# work.net
KiCad netlist of a schematic drawn in Altium Designer
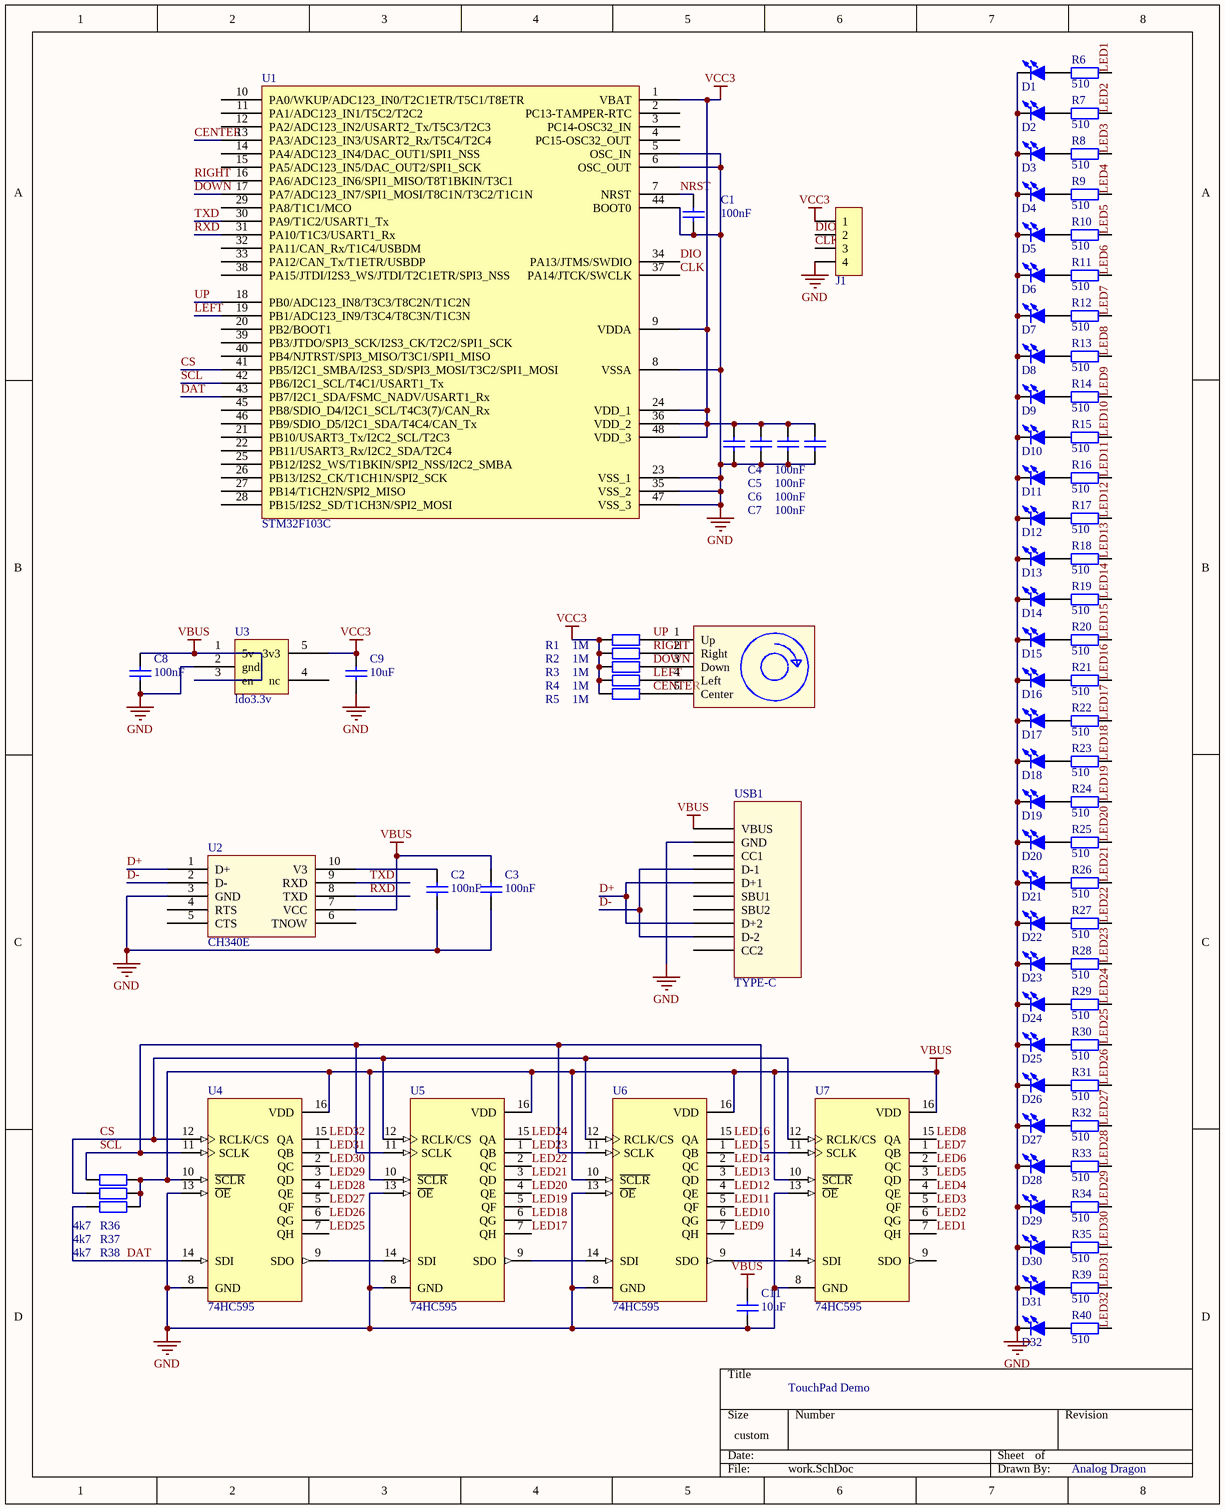
[diagram p0: work.SchDoc]

(export (version "E")
  (design (tool "Eeschema 10.0.6"))
  (components
    (comp (ref "*1")
      (value "TouchPad-R")
      (footprint "TouchPad-R")
      (libsource (lib "fszhang") (part "TouchPad-R"))
    )
    (comp (ref "C1")
      (value "100nF")
      (footprint "C-RAD-0603")
      (description "无极性电容")
      (fields (field (name "Comment") "Cap") (field (name "PUBLISHER") "Altium Limited"))
      (libsource (lib "fszhang") (part "Cap"))
    )
    (comp (ref "C2")
      (value "100nF")
      (footprint "C-RAD-0603")
      (description "无极性电容")
      (fields (field (name "Comment") "Cap") (field (name "PUBLISHER") "Altium Limited"))
      (libsource (lib "fszhang") (part "Cap"))
    )
    (comp (ref "C3")
      (value "100nF")
      (footprint "C-RAD-0603")
      (description "无极性电容")
      (fields (field (name "Comment") "Cap") (field (name "PUBLISHER") "Altium Limited"))
      (libsource (lib "fszhang") (part "Cap"))
    )
    (comp (ref "C4")
      (value "100nF")
      (footprint "C-RAD-0603")
      (description "无极性电容")
      (fields (field (name "Comment") "Cap") (field (name "PUBLISHER") "Altium Limited"))
      (libsource (lib "fszhang") (part "Cap"))
    )
    (comp (ref "C5")
      (value "100nF")
      (footprint "C-RAD-0603")
      (description "无极性电容")
      (fields (field (name "Comment") "Cap") (field (name "PUBLISHER") "Altium Limited"))
      (libsource (lib "fszhang") (part "Cap"))
    )
    (comp (ref "C6")
      (value "100nF")
      (footprint "C-RAD-0603")
      (description "无极性电容")
      (fields (field (name "Comment") "Cap") (field (name "PUBLISHER") "Altium Limited"))
      (libsource (lib "fszhang") (part "Cap"))
    )
    (comp (ref "C7")
      (value "100nF")
      (footprint "C-RAD-0603")
      (description "无极性电容")
      (fields (field (name "Comment") "Cap") (field (name "PUBLISHER") "Altium Limited"))
      (libsource (lib "fszhang") (part "Cap"))
    )
    (comp (ref "C8")
      (value "100nF")
      (footprint "C-RAD-3528")
      (description "无极性电容")
      (fields (field (name "Comment") "Cap") (field (name "PUBLISHER") "Altium Limited"))
      (libsource (lib "fszhang") (part "Cap"))
    )
    (comp (ref "C9")
      (value "10uF")
      (footprint "C-RAD-0805")
      (description "无极性电容")
      (fields (field (name "Comment") "Cap") (field (name "PUBLISHER") "Altium Limited"))
      (libsource (lib "fszhang") (part "Cap"))
    )
    (comp (ref "C11")
      (value "10uF")
      (footprint "C-RAD-0805")
      (description "无极性电容")
      (fields (field (name "Comment") "Cap") (field (name "PUBLISHER") "Altium Limited"))
      (libsource (lib "fszhang") (part "Cap"))
    )
    (comp (ref "D1")
      (value "~")
      (footprint "LED 0805W")
      (description "贴片LED")
      (libsource (lib "9.1   - LED") (part "LED-SMD"))
    )
    (comp (ref "D2")
      (value "~")
      (footprint "LED 0805W")
      (description "贴片LED")
      (libsource (lib "9.1   - LED") (part "LED-SMD"))
    )
    (comp (ref "D3")
      (value "~")
      (footprint "LED 0805W")
      (description "贴片LED")
      (libsource (lib "9.1   - LED") (part "LED-SMD"))
    )
    (comp (ref "D4")
      (value "~")
      (footprint "LED 0805W")
      (description "贴片LED")
      (libsource (lib "9.1   - LED") (part "LED-SMD"))
    )
    (comp (ref "D5")
      (value "~")
      (footprint "LED 0805W")
      (description "贴片LED")
      (libsource (lib "9.1   - LED") (part "LED-SMD"))
    )
    (comp (ref "D6")
      (value "~")
      (footprint "LED 0805W")
      (description "贴片LED")
      (libsource (lib "9.1   - LED") (part "LED-SMD"))
    )
    (comp (ref "D7")
      (value "~")
      (footprint "LED 0805W")
      (description "贴片LED")
      (libsource (lib "9.1   - LED") (part "LED-SMD"))
    )
    (comp (ref "D8")
      (value "~")
      (footprint "LED 0805W")
      (description "贴片LED")
      (libsource (lib "9.1   - LED") (part "LED-SMD"))
    )
    (comp (ref "D9")
      (value "~")
      (footprint "LED 0805W")
      (description "贴片LED")
      (libsource (lib "9.1   - LED") (part "LED-SMD"))
    )
    (comp (ref "D10")
      (value "~")
      (footprint "LED 0805W")
      (description "贴片LED")
      (libsource (lib "9.1   - LED") (part "LED-SMD"))
    )
    (comp (ref "D11")
      (value "~")
      (footprint "LED 0805W")
      (description "贴片LED")
      (libsource (lib "9.1   - LED") (part "LED-SMD"))
    )
    (comp (ref "D12")
      (value "~")
      (footprint "LED 0805W")
      (description "贴片LED")
      (libsource (lib "9.1   - LED") (part "LED-SMD"))
    )
    (comp (ref "D13")
      (value "~")
      (footprint "LED 0805W")
      (description "贴片LED")
      (libsource (lib "9.1   - LED") (part "LED-SMD"))
    )
    (comp (ref "D14")
      (value "~")
      (footprint "LED 0805W")
      (description "贴片LED")
      (libsource (lib "9.1   - LED") (part "LED-SMD"))
    )
    (comp (ref "D15")
      (value "~")
      (footprint "LED 0805W")
      (description "贴片LED")
      (libsource (lib "9.1   - LED") (part "LED-SMD"))
    )
    (comp (ref "D16")
      (value "~")
      (footprint "LED 0805W")
      (description "贴片LED")
      (libsource (lib "9.1   - LED") (part "LED-SMD"))
    )
    (comp (ref "D17")
      (value "~")
      (footprint "LED 0805W")
      (description "贴片LED")
      (libsource (lib "9.1   - LED") (part "LED-SMD"))
    )
    (comp (ref "D18")
      (value "~")
      (footprint "LED 0805W")
      (description "贴片LED")
      (libsource (lib "9.1   - LED") (part "LED-SMD"))
    )
    (comp (ref "D19")
      (value "~")
      (footprint "LED 0805W")
      (description "贴片LED")
      (libsource (lib "9.1   - LED") (part "LED-SMD"))
    )
    (comp (ref "D20")
      (value "~")
      (footprint "LED 0805W")
      (description "贴片LED")
      (libsource (lib "9.1   - LED") (part "LED-SMD"))
    )
    (comp (ref "D21")
      (value "~")
      (footprint "LED 0805W")
      (description "贴片LED")
      (libsource (lib "9.1   - LED") (part "LED-SMD"))
    )
    (comp (ref "D22")
      (value "~")
      (footprint "LED 0805W")
      (description "贴片LED")
      (libsource (lib "9.1   - LED") (part "LED-SMD"))
    )
    (comp (ref "D23")
      (value "~")
      (footprint "LED 0805W")
      (description "贴片LED")
      (libsource (lib "9.1   - LED") (part "LED-SMD"))
    )
    (comp (ref "D24")
      (value "~")
      (footprint "LED 0805W")
      (description "贴片LED")
      (libsource (lib "9.1   - LED") (part "LED-SMD"))
    )
    (comp (ref "D25")
      (value "~")
      (footprint "LED 0805W")
      (description "贴片LED")
      (libsource (lib "9.1   - LED") (part "LED-SMD"))
    )
    (comp (ref "D26")
      (value "~")
      (footprint "LED 0805W")
      (description "贴片LED")
      (libsource (lib "9.1   - LED") (part "LED-SMD"))
    )
    (comp (ref "D27")
      (value "~")
      (footprint "LED 0805W")
      (description "贴片LED")
      (libsource (lib "9.1   - LED") (part "LED-SMD"))
    )
    (comp (ref "D28")
      (value "~")
      (footprint "LED 0805W")
      (description "贴片LED")
      (libsource (lib "9.1   - LED") (part "LED-SMD"))
    )
    (comp (ref "D29")
      (value "~")
      (footprint "LED 0805W")
      (description "贴片LED")
      (libsource (lib "9.1   - LED") (part "LED-SMD"))
    )
    (comp (ref "D30")
      (value "~")
      (footprint "LED 0805W")
      (description "贴片LED")
      (libsource (lib "9.1   - LED") (part "LED-SMD"))
    )
    (comp (ref "D31")
      (value "~")
      (footprint "LED 0805W")
      (description "贴片LED")
      (libsource (lib "9.1   - LED") (part "LED-SMD"))
    )
    (comp (ref "D32")
      (value "~")
      (footprint "LED 0805W")
      (description "贴片LED")
      (libsource (lib "9.1   - LED") (part "LED-SMD"))
    )
    (comp (ref "J1")
      (value "HDR-1X4")
      (footprint "HDR2.0-LI-4P")
      (description "4P接插件")
      (libsource (lib "4.5   - 接插件-脚距2.0") (part "Header 4"))
    )
    (comp (ref "R1")
      (value "1M")
      (footprint "0603-1")
      (description "贴片电阻")
      (fields (field (name "Comment") "Res1") (field (name "PUBLISHER") "Altium Limited"))
      (libsource (lib "fszhang") (part "Res1"))
    )
    (comp (ref "R2")
      (value "1M")
      (footprint "0603-1")
      (description "贴片电阻")
      (fields (field (name "Comment") "Res1") (field (name "PUBLISHER") "Altium Limited"))
      (libsource (lib "fszhang") (part "Res1"))
    )
    (comp (ref "R3")
      (value "1M")
      (footprint "0603-1")
      (description "贴片电阻")
      (fields (field (name "Comment") "Res1") (field (name "PUBLISHER") "Altium Limited"))
      (libsource (lib "fszhang") (part "Res1"))
    )
    (comp (ref "R4")
      (value "1M")
      (footprint "0603-1")
      (description "贴片电阻")
      (fields (field (name "Comment") "Res1") (field (name "PUBLISHER") "Altium Limited"))
      (libsource (lib "fszhang") (part "Res1"))
    )
    (comp (ref "R5")
      (value "1M")
      (footprint "0603-1")
      (description "贴片电阻")
      (fields (field (name "Comment") "Res1") (field (name "PUBLISHER") "Altium Limited"))
      (libsource (lib "fszhang") (part "Res1"))
    )
    (comp (ref "R6")
      (value "510")
      (footprint "0603-1")
      (description "贴片电阻")
      (fields (field (name "Comment") "Res1") (field (name "PUBLISHER") "Altium Limited"))
      (libsource (lib "fszhang") (part "Res1"))
    )
    (comp (ref "R7")
      (value "510")
      (footprint "0603-1")
      (description "贴片电阻")
      (fields (field (name "Comment") "Res1") (field (name "PUBLISHER") "Altium Limited"))
      (libsource (lib "fszhang") (part "Res1"))
    )
    (comp (ref "R8")
      (value "510")
      (footprint "0603-1")
      (description "贴片电阻")
      (fields (field (name "Comment") "Res1") (field (name "PUBLISHER") "Altium Limited"))
      (libsource (lib "fszhang") (part "Res1"))
    )
    (comp (ref "R9")
      (value "510")
      (footprint "0603-1")
      (description "贴片电阻")
      (fields (field (name "Comment") "Res1") (field (name "PUBLISHER") "Altium Limited"))
      (libsource (lib "fszhang") (part "Res1"))
    )
    (comp (ref "R10")
      (value "510")
      (footprint "0603-1")
      (description "贴片电阻")
      (fields (field (name "Comment") "Res1") (field (name "PUBLISHER") "Altium Limited"))
      (libsource (lib "fszhang") (part "Res1"))
    )
    (comp (ref "R11")
      (value "510")
      (footprint "0603-1")
      (description "贴片电阻")
      (fields (field (name "Comment") "Res1") (field (name "PUBLISHER") "Altium Limited"))
      (libsource (lib "fszhang") (part "Res1"))
    )
    (comp (ref "R12")
      (value "510")
      (footprint "0603-1")
      (description "贴片电阻")
      (fields (field (name "Comment") "Res1") (field (name "PUBLISHER") "Altium Limited"))
      (libsource (lib "fszhang") (part "Res1"))
    )
    (comp (ref "R13")
      (value "510")
      (footprint "0603-1")
      (description "贴片电阻")
      (fields (field (name "Comment") "Res1") (field (name "PUBLISHER") "Altium Limited"))
      (libsource (lib "fszhang") (part "Res1"))
    )
    (comp (ref "R14")
      (value "510")
      (footprint "0603-1")
      (description "贴片电阻")
      (fields (field (name "Comment") "Res1") (field (name "PUBLISHER") "Altium Limited"))
      (libsource (lib "fszhang") (part "Res1"))
    )
    (comp (ref "R15")
      (value "510")
      (footprint "0603-1")
      (description "贴片电阻")
      (fields (field (name "Comment") "Res1") (field (name "PUBLISHER") "Altium Limited"))
      (libsource (lib "fszhang") (part "Res1"))
    )
    (comp (ref "R16")
      (value "510")
      (footprint "0603-1")
      (description "贴片电阻")
      (fields (field (name "Comment") "Res1") (field (name "PUBLISHER") "Altium Limited"))
      (libsource (lib "fszhang") (part "Res1"))
    )
    (comp (ref "R17")
      (value "510")
      (footprint "0603-1")
      (description "贴片电阻")
      (fields (field (name "Comment") "Res1") (field (name "PUBLISHER") "Altium Limited"))
      (libsource (lib "fszhang") (part "Res1"))
    )
    (comp (ref "R18")
      (value "510")
      (footprint "0603-1")
      (description "贴片电阻")
      (fields (field (name "Comment") "Res1") (field (name "PUBLISHER") "Altium Limited"))
      (libsource (lib "fszhang") (part "Res1"))
    )
    (comp (ref "R19")
      (value "510")
      (footprint "0603-1")
      (description "贴片电阻")
      (fields (field (name "Comment") "Res1") (field (name "PUBLISHER") "Altium Limited"))
      (libsource (lib "fszhang") (part "Res1"))
    )
    (comp (ref "R20")
      (value "510")
      (footprint "0603-1")
      (description "贴片电阻")
      (fields (field (name "Comment") "Res1") (field (name "PUBLISHER") "Altium Limited"))
      (libsource (lib "fszhang") (part "Res1"))
    )
    (comp (ref "R21")
      (value "510")
      (footprint "0603-1")
      (description "贴片电阻")
      (fields (field (name "Comment") "Res1") (field (name "PUBLISHER") "Altium Limited"))
      (libsource (lib "fszhang") (part "Res1"))
    )
    (comp (ref "R22")
      (value "510")
      (footprint "0603-1")
      (description "贴片电阻")
      (fields (field (name "Comment") "Res1") (field (name "PUBLISHER") "Altium Limited"))
      (libsource (lib "fszhang") (part "Res1"))
    )
    (comp (ref "R23")
      (value "510")
      (footprint "0603-1")
      (description "贴片电阻")
      (fields (field (name "Comment") "Res1") (field (name "PUBLISHER") "Altium Limited"))
      (libsource (lib "fszhang") (part "Res1"))
    )
    (comp (ref "R24")
      (value "510")
      (footprint "0603-1")
      (description "贴片电阻")
      (fields (field (name "Comment") "Res1") (field (name "PUBLISHER") "Altium Limited"))
      (libsource (lib "fszhang") (part "Res1"))
    )
    (comp (ref "R25")
      (value "510")
      (footprint "0603-1")
      (description "贴片电阻")
      (fields (field (name "Comment") "Res1") (field (name "PUBLISHER") "Altium Limited"))
      (libsource (lib "fszhang") (part "Res1"))
    )
    (comp (ref "R26")
      (value "510")
      (footprint "0603-1")
      (description "贴片电阻")
      (fields (field (name "Comment") "Res1") (field (name "PUBLISHER") "Altium Limited"))
      (libsource (lib "fszhang") (part "Res1"))
    )
    (comp (ref "R27")
      (value "510")
      (footprint "0603-1")
      (description "贴片电阻")
      (fields (field (name "Comment") "Res1") (field (name "PUBLISHER") "Altium Limited"))
      (libsource (lib "fszhang") (part "Res1"))
    )
    (comp (ref "R28")
      (value "510")
      (footprint "0603-1")
      (description "贴片电阻")
      (fields (field (name "Comment") "Res1") (field (name "PUBLISHER") "Altium Limited"))
      (libsource (lib "fszhang") (part "Res1"))
    )
    (comp (ref "R29")
      (value "510")
      (footprint "0603-1")
      (description "贴片电阻")
      (fields (field (name "Comment") "Res1") (field (name "PUBLISHER") "Altium Limited"))
      (libsource (lib "fszhang") (part "Res1"))
    )
    (comp (ref "R30")
      (value "510")
      (footprint "0603-1")
      (description "贴片电阻")
      (fields (field (name "Comment") "Res1") (field (name "PUBLISHER") "Altium Limited"))
      (libsource (lib "fszhang") (part "Res1"))
    )
    (comp (ref "R31")
      (value "510")
      (footprint "0603-1")
      (description "贴片电阻")
      (fields (field (name "Comment") "Res1") (field (name "PUBLISHER") "Altium Limited"))
      (libsource (lib "fszhang") (part "Res1"))
    )
    (comp (ref "R32")
      (value "510")
      (footprint "0603-1")
      (description "贴片电阻")
      (fields (field (name "Comment") "Res1") (field (name "PUBLISHER") "Altium Limited"))
      (libsource (lib "fszhang") (part "Res1"))
    )
    (comp (ref "R33")
      (value "510")
      (footprint "0603-1")
      (description "贴片电阻")
      (fields (field (name "Comment") "Res1") (field (name "PUBLISHER") "Altium Limited"))
      (libsource (lib "fszhang") (part "Res1"))
    )
    (comp (ref "R34")
      (value "510")
      (footprint "0603-1")
      (description "贴片电阻")
      (fields (field (name "Comment") "Res1") (field (name "PUBLISHER") "Altium Limited"))
      (libsource (lib "fszhang") (part "Res1"))
    )
    (comp (ref "R35")
      (value "510")
      (footprint "0603-1")
      (description "贴片电阻")
      (fields (field (name "Comment") "Res1") (field (name "PUBLISHER") "Altium Limited"))
      (libsource (lib "fszhang") (part "Res1"))
    )
    (comp (ref "R36")
      (value "4k7")
      (footprint "0603-1")
      (description "贴片电阻")
      (fields (field (name "Comment") "Res1") (field (name "PUBLISHER") "Altium Limited"))
      (libsource (lib "fszhang") (part "Res1"))
    )
    (comp (ref "R37")
      (value "4k7")
      (footprint "0603-1")
      (description "贴片电阻")
      (fields (field (name "Comment") "Res1") (field (name "PUBLISHER") "Altium Limited"))
      (libsource (lib "fszhang") (part "Res1"))
    )
    (comp (ref "R38")
      (value "4k7")
      (footprint "0603-1")
      (description "贴片电阻")
      (fields (field (name "Comment") "Res1") (field (name "PUBLISHER") "Altium Limited"))
      (libsource (lib "fszhang") (part "Res1"))
    )
    (comp (ref "R39")
      (value "510")
      (footprint "0603-1")
      (description "贴片电阻")
      (fields (field (name "Comment") "Res1") (field (name "PUBLISHER") "Altium Limited"))
      (libsource (lib "fszhang") (part "Res1"))
    )
    (comp (ref "R40")
      (value "510")
      (footprint "0603-1")
      (description "贴片电阻")
      (fields (field (name "Comment") "Res1") (field (name "PUBLISHER") "Altium Limited"))
      (libsource (lib "fszhang") (part "Res1"))
    )
    (comp (ref "U1")
      (value "STM32F103C")
      (footprint "LQFP-48_M")
      (description "STM32单片机48引脚")
      (libsource (lib "fszhang") (part "STM32F103C"))
    )
    (comp (ref "U2") (value "CH340E") (footprint "MSOP10_M") (libsource (lib "1") (part "CH340E")))
    (comp (ref "U3") (value "ldo3.3v") (footprint "SOT23-5") (libsource (lib "3.3ldo") (part "Component_1")))
    (comp (ref "U4")
      (value "74HC595")
      (footprint "NSO16_M")
      (description "移位寄存器")
      (fields (field (name "PUBLISHER") "Altium Limited"))
      (libsource (lib "fszhang") (part "74HC595"))
    )
    (comp (ref "U5")
      (value "74HC595")
      (footprint "NSO16_M")
      (description "移位寄存器")
      (fields (field (name "PUBLISHER") "Altium Limited"))
      (libsource (lib "fszhang") (part "74HC595"))
    )
    (comp (ref "U6")
      (value "74HC595")
      (footprint "NSO16_M")
      (description "移位寄存器")
      (fields (field (name "PUBLISHER") "Altium Limited"))
      (libsource (lib "fszhang") (part "74HC595"))
    )
    (comp (ref "U7")
      (value "74HC595")
      (footprint "NSO16_M")
      (description "移位寄存器")
      (fields (field (name "PUBLISHER") "Altium Limited"))
      (libsource (lib "fszhang") (part "74HC595"))
    )
    (comp (ref "USB1") (value "TYPE-C") (footprint "TYPE-C") (libsource (lib "1") (part "USB-C")))
  )
  (nets
    (net (code "1") (name "/CENTER") (class "Default")
      (node (ref "*1") (pin "5") (pinfunction "Center_5") (pintype "passive"))
      (node (ref "R5") (pin "2") (pinfunction "2_2") (pintype "passive"))
      (node (ref "U1") (pin "13") (pinfunction "PA3/ADC123_IN3/USART2_Rx/T5C4/T2C4_13") (pintype "passive"))
    )
    (net (code "2") (name "/CLK") (class "Default")
      (node (ref "J1") (pin "3") (pinfunction "3_3") (pintype "passive"))
      (node (ref "U1") (pin "37") (pinfunction "PA14/JTCK/SWCLK_37") (pintype "passive"))
    )
    (net (code "3") (name "/CS") (class "Default")
      (node (ref "R37") (pin "1") (pinfunction "1_1") (pintype "passive"))
      (node (ref "U1") (pin "41") (pinfunction "PB5/I2C1_SMBA/I2S3_SD/SPI3_MOSI/T3C2/SPI1_MOSI_41") (pintype "passive"))
      (node (ref "U4") (pin "12") (pinfunction "RCLK/CS_12") (pintype "input"))
      (node (ref "U5") (pin "12") (pinfunction "RCLK/CS_12") (pintype "input"))
      (node (ref "U6") (pin "12") (pinfunction "RCLK/CS_12") (pintype "input"))
      (node (ref "U7") (pin "12") (pinfunction "RCLK/CS_12") (pintype "input"))
    )
    (net (code "4") (name "/D+") (class "Default")
      (node (ref "U2") (pin "1") (pinfunction "D+_1") (pintype "passive"))
      (node (ref "USB1") (pin "D+1") (pinfunction "D+1_D+1") (pintype "passive"))
      (node (ref "USB1") (pin "D+2") (pinfunction "D+2_D+2") (pintype "passive"))
    )
    (net (code "5") (name "/D-") (class "Default")
      (node (ref "U2") (pin "2") (pinfunction "D-_2") (pintype "passive"))
      (node (ref "USB1") (pin "D-1") (pinfunction "D-1_D-1") (pintype "passive"))
      (node (ref "USB1") (pin "D-2") (pinfunction "D-2_D-2") (pintype "passive"))
    )
    (net (code "6") (name "/DAT") (class "Default")
      (node (ref "R38") (pin "1") (pinfunction "1_1") (pintype "passive"))
      (node (ref "U1") (pin "43") (pinfunction "PB7/I2C1_SDA/FSMC_NADV/USART1_Rx_43") (pintype "passive"))
      (node (ref "U4") (pin "14") (pinfunction "SDI_14") (pintype "input"))
    )
    (net (code "7") (name "/DIO") (class "Default")
      (node (ref "J1") (pin "2") (pinfunction "2_2") (pintype "passive"))
      (node (ref "U1") (pin "34") (pinfunction "PA13/JTMS/SWDIO_34") (pintype "passive"))
    )
    (net (code "8") (name "/DOWN") (class "Default")
      (node (ref "*1") (pin "3") (pinfunction "Down_3") (pintype "passive"))
      (node (ref "R3") (pin "2") (pinfunction "2_2") (pintype "passive"))
      (node (ref "U1") (pin "17") (pinfunction "PA7/ADC123_IN7/SPI1_MOSI/T8C1N/T3C2/T1C1N_17") (pintype "passive"))
    )
    (net (code "9") (name "/LED1") (class "Default")
      (node (ref "R6") (pin "2") (pinfunction "2_2") (pintype "passive"))
      (node (ref "U7") (pin "7") (pinfunction "QH_7") (pintype "tri_state"))
    )
    (net (code "10") (name "/LED2") (class "Default")
      (node (ref "R7") (pin "2") (pinfunction "2_2") (pintype "passive"))
      (node (ref "U7") (pin "6") (pinfunction "QG_6") (pintype "tri_state"))
    )
    (net (code "11") (name "/LED3") (class "Default")
      (node (ref "R8") (pin "2") (pinfunction "2_2") (pintype "passive"))
      (node (ref "U7") (pin "5") (pinfunction "QF_5") (pintype "tri_state"))
    )
    (net (code "12") (name "/LED4") (class "Default")
      (node (ref "R9") (pin "2") (pinfunction "2_2") (pintype "passive"))
      (node (ref "U7") (pin "4") (pinfunction "QE_4") (pintype "tri_state"))
    )
    (net (code "13") (name "/LED5") (class "Default")
      (node (ref "R10") (pin "2") (pinfunction "2_2") (pintype "passive"))
      (node (ref "U7") (pin "3") (pinfunction "QD_3") (pintype "tri_state"))
    )
    (net (code "14") (name "/LED6") (class "Default")
      (node (ref "R11") (pin "2") (pinfunction "2_2") (pintype "passive"))
      (node (ref "U7") (pin "2") (pinfunction "QC_2") (pintype "tri_state"))
    )
    (net (code "15") (name "/LED7") (class "Default")
      (node (ref "R12") (pin "2") (pinfunction "2_2") (pintype "passive"))
      (node (ref "U7") (pin "1") (pinfunction "QB_1") (pintype "tri_state"))
    )
    (net (code "16") (name "/LED8") (class "Default")
      (node (ref "R13") (pin "2") (pinfunction "2_2") (pintype "passive"))
      (node (ref "U7") (pin "15") (pinfunction "QA_15") (pintype "tri_state"))
    )
    (net (code "17") (name "/LED9") (class "Default")
      (node (ref "R14") (pin "2") (pinfunction "2_2") (pintype "passive"))
      (node (ref "U6") (pin "7") (pinfunction "QH_7") (pintype "tri_state"))
    )
    (net (code "18") (name "/LED10") (class "Default")
      (node (ref "R15") (pin "2") (pinfunction "2_2") (pintype "passive"))
      (node (ref "U6") (pin "6") (pinfunction "QG_6") (pintype "tri_state"))
    )
    (net (code "19") (name "/LED11") (class "Default")
      (node (ref "R16") (pin "2") (pinfunction "2_2") (pintype "passive"))
      (node (ref "U6") (pin "5") (pinfunction "QF_5") (pintype "tri_state"))
    )
    (net (code "20") (name "/LED12") (class "Default")
      (node (ref "R17") (pin "2") (pinfunction "2_2") (pintype "passive"))
      (node (ref "U6") (pin "4") (pinfunction "QE_4") (pintype "tri_state"))
    )
    (net (code "21") (name "/LED13") (class "Default")
      (node (ref "R18") (pin "2") (pinfunction "2_2") (pintype "passive"))
      (node (ref "U6") (pin "3") (pinfunction "QD_3") (pintype "tri_state"))
    )
    (net (code "22") (name "/LED14") (class "Default")
      (node (ref "R19") (pin "2") (pinfunction "2_2") (pintype "passive"))
      (node (ref "U6") (pin "2") (pinfunction "QC_2") (pintype "tri_state"))
    )
    (net (code "23") (name "/LED15") (class "Default")
      (node (ref "R20") (pin "2") (pinfunction "2_2") (pintype "passive"))
      (node (ref "U6") (pin "1") (pinfunction "QB_1") (pintype "tri_state"))
    )
    (net (code "24") (name "/LED16") (class "Default")
      (node (ref "R21") (pin "2") (pinfunction "2_2") (pintype "passive"))
      (node (ref "U6") (pin "15") (pinfunction "QA_15") (pintype "tri_state"))
    )
    (net (code "25") (name "/LED17") (class "Default")
      (node (ref "R22") (pin "2") (pinfunction "2_2") (pintype "passive"))
      (node (ref "U5") (pin "7") (pinfunction "QH_7") (pintype "tri_state"))
    )
    (net (code "26") (name "/LED18") (class "Default")
      (node (ref "R23") (pin "2") (pinfunction "2_2") (pintype "passive"))
      (node (ref "U5") (pin "6") (pinfunction "QG_6") (pintype "tri_state"))
    )
    (net (code "27") (name "/LED19") (class "Default")
      (node (ref "R24") (pin "2") (pinfunction "2_2") (pintype "passive"))
      (node (ref "U5") (pin "5") (pinfunction "QF_5") (pintype "tri_state"))
    )
    (net (code "28") (name "/LED20") (class "Default")
      (node (ref "R25") (pin "2") (pinfunction "2_2") (pintype "passive"))
      (node (ref "U5") (pin "4") (pinfunction "QE_4") (pintype "tri_state"))
    )
    (net (code "29") (name "/LED21") (class "Default")
      (node (ref "R26") (pin "2") (pinfunction "2_2") (pintype "passive"))
      (node (ref "U5") (pin "3") (pinfunction "QD_3") (pintype "tri_state"))
    )
    (net (code "30") (name "/LED22") (class "Default")
      (node (ref "R27") (pin "2") (pinfunction "2_2") (pintype "passive"))
      (node (ref "U5") (pin "2") (pinfunction "QC_2") (pintype "tri_state"))
    )
    (net (code "31") (name "/LED23") (class "Default")
      (node (ref "R28") (pin "2") (pinfunction "2_2") (pintype "passive"))
      (node (ref "U5") (pin "1") (pinfunction "QB_1") (pintype "tri_state"))
    )
    (net (code "32") (name "/LED24") (class "Default")
      (node (ref "R29") (pin "2") (pinfunction "2_2") (pintype "passive"))
      (node (ref "U5") (pin "15") (pinfunction "QA_15") (pintype "tri_state"))
    )
    (net (code "33") (name "/LED25") (class "Default")
      (node (ref "R30") (pin "2") (pinfunction "2_2") (pintype "passive"))
      (node (ref "U4") (pin "7") (pinfunction "QH_7") (pintype "tri_state"))
    )
    (net (code "34") (name "/LED26") (class "Default")
      (node (ref "R31") (pin "2") (pinfunction "2_2") (pintype "passive"))
      (node (ref "U4") (pin "6") (pinfunction "QG_6") (pintype "tri_state"))
    )
    (net (code "35") (name "/LED27") (class "Default")
      (node (ref "R32") (pin "2") (pinfunction "2_2") (pintype "passive"))
      (node (ref "U4") (pin "5") (pinfunction "QF_5") (pintype "tri_state"))
    )
    (net (code "36") (name "/LED28") (class "Default")
      (node (ref "R33") (pin "2") (pinfunction "2_2") (pintype "passive"))
      (node (ref "U4") (pin "4") (pinfunction "QE_4") (pintype "tri_state"))
    )
    (net (code "37") (name "/LED29") (class "Default")
      (node (ref "R34") (pin "2") (pinfunction "2_2") (pintype "passive"))
      (node (ref "U4") (pin "3") (pinfunction "QD_3") (pintype "tri_state"))
    )
    (net (code "38") (name "/LED30") (class "Default")
      (node (ref "R35") (pin "2") (pinfunction "2_2") (pintype "passive"))
      (node (ref "U4") (pin "2") (pinfunction "QC_2") (pintype "tri_state"))
    )
    (net (code "39") (name "/LED31") (class "Default")
      (node (ref "R39") (pin "2") (pinfunction "2_2") (pintype "passive"))
      (node (ref "U4") (pin "1") (pinfunction "QB_1") (pintype "tri_state"))
    )
    (net (code "40") (name "/LED32") (class "Default")
      (node (ref "R40") (pin "2") (pinfunction "2_2") (pintype "passive"))
      (node (ref "U4") (pin "15") (pinfunction "QA_15") (pintype "tri_state"))
    )
    (net (code "41") (name "/LEFT") (class "Default")
      (node (ref "*1") (pin "4") (pinfunction "Left_4") (pintype "passive"))
      (node (ref "R4") (pin "2") (pinfunction "2_2") (pintype "passive"))
      (node (ref "U1") (pin "19") (pinfunction "PB1/ADC123_IN9/T3C4/T8C3N/T1C3N_19") (pintype "passive"))
    )
    (net (code "42") (name "/NRST") (class "Default")
      (node (ref "C1") (pin "2") (pinfunction "2_2") (pintype "passive"))
      (node (ref "U1") (pin "7") (pinfunction "NRST_7") (pintype "passive"))
    )
    (net (code "43") (name "/RIGHT") (class "Default")
      (node (ref "*1") (pin "2") (pinfunction "Right_2") (pintype "passive"))
      (node (ref "R2") (pin "2") (pinfunction "2_2") (pintype "passive"))
      (node (ref "U1") (pin "16") (pinfunction "PA6/ADC123_IN6/SPI1_MISO/T8T1BKIN/T3C1_16") (pintype "passive"))
    )
    (net (code "44") (name "/RXD") (class "Default")
      (node (ref "U1") (pin "31") (pinfunction "PA10/T1C3/USART1_Rx_31") (pintype "passive"))
      (node (ref "U2") (pin "8") (pinfunction "TXD_8") (pintype "passive"))
    )
    (net (code "45") (name "/SCL") (class "Default")
      (node (ref "R36") (pin "1") (pinfunction "1_1") (pintype "passive"))
      (node (ref "U1") (pin "42") (pinfunction "PB6/I2C1_SCL/T4C1/USART1_Tx_42") (pintype "passive"))
      (node (ref "U4") (pin "11") (pinfunction "SCLK_11") (pintype "input"))
      (node (ref "U5") (pin "11") (pinfunction "SCLK_11") (pintype "input"))
      (node (ref "U6") (pin "11") (pinfunction "SCLK_11") (pintype "input"))
      (node (ref "U7") (pin "11") (pinfunction "SCLK_11") (pintype "input"))
    )
    (net (code "46") (name "/TXD") (class "Default")
      (node (ref "U1") (pin "30") (pinfunction "PA9/T1C2/USART1_Tx_30") (pintype "passive"))
      (node (ref "U2") (pin "9") (pinfunction "RXD_9") (pintype "passive"))
    )
    (net (code "47") (name "/UP") (class "Default")
      (node (ref "*1") (pin "1") (pinfunction "Up_1") (pintype "passive"))
      (node (ref "R1") (pin "2") (pinfunction "2_2") (pintype "passive"))
      (node (ref "U1") (pin "18") (pinfunction "PB0/ADC123_IN8/T3C3/T8C2N/T1C2N_18") (pintype "passive"))
    )
    (net (code "48") (name "GND") (class "Default")
      (node (ref "C1") (pin "1") (pinfunction "1_1") (pintype "passive"))
      (node (ref "C11") (pin "1") (pinfunction "1_1") (pintype "passive"))
      (node (ref "C2") (pin "1") (pinfunction "1_1") (pintype "passive"))
      (node (ref "C3") (pin "1") (pinfunction "1_1") (pintype "passive"))
      (node (ref "C4") (pin "1") (pinfunction "1_1") (pintype "passive"))
      (node (ref "C5") (pin "1") (pinfunction "1_1") (pintype "passive"))
      (node (ref "C6") (pin "1") (pinfunction "1_1") (pintype "passive"))
      (node (ref "C7") (pin "1") (pinfunction "1_1") (pintype "passive"))
      (node (ref "C8") (pin "1") (pinfunction "1_1") (pintype "passive"))
      (node (ref "C9") (pin "1") (pinfunction "1_1") (pintype "passive"))
      (node (ref "D1") (pin "2") (pinfunction "K_2") (pintype "passive"))
      (node (ref "D10") (pin "2") (pinfunction "K_2") (pintype "passive"))
      (node (ref "D11") (pin "2") (pinfunction "K_2") (pintype "passive"))
      (node (ref "D12") (pin "2") (pinfunction "K_2") (pintype "passive"))
      (node (ref "D13") (pin "2") (pinfunction "K_2") (pintype "passive"))
      (node (ref "D14") (pin "2") (pinfunction "K_2") (pintype "passive"))
      (node (ref "D15") (pin "2") (pinfunction "K_2") (pintype "passive"))
      (node (ref "D16") (pin "2") (pinfunction "K_2") (pintype "passive"))
      (node (ref "D17") (pin "2") (pinfunction "K_2") (pintype "passive"))
      (node (ref "D18") (pin "2") (pinfunction "K_2") (pintype "passive"))
      (node (ref "D19") (pin "2") (pinfunction "K_2") (pintype "passive"))
      (node (ref "D2") (pin "2") (pinfunction "K_2") (pintype "passive"))
      (node (ref "D20") (pin "2") (pinfunction "K_2") (pintype "passive"))
      (node (ref "D21") (pin "2") (pinfunction "K_2") (pintype "passive"))
      (node (ref "D22") (pin "2") (pinfunction "K_2") (pintype "passive"))
      (node (ref "D23") (pin "2") (pinfunction "K_2") (pintype "passive"))
      (node (ref "D24") (pin "2") (pinfunction "K_2") (pintype "passive"))
      (node (ref "D25") (pin "2") (pinfunction "K_2") (pintype "passive"))
      (node (ref "D26") (pin "2") (pinfunction "K_2") (pintype "passive"))
      (node (ref "D27") (pin "2") (pinfunction "K_2") (pintype "passive"))
      (node (ref "D28") (pin "2") (pinfunction "K_2") (pintype "passive"))
      (node (ref "D29") (pin "2") (pinfunction "K_2") (pintype "passive"))
      (node (ref "D3") (pin "2") (pinfunction "K_2") (pintype "passive"))
      (node (ref "D30") (pin "2") (pinfunction "K_2") (pintype "passive"))
      (node (ref "D31") (pin "2") (pinfunction "K_2") (pintype "passive"))
      (node (ref "D32") (pin "2") (pinfunction "K_2") (pintype "passive"))
      (node (ref "D4") (pin "2") (pinfunction "K_2") (pintype "passive"))
      (node (ref "D5") (pin "2") (pinfunction "K_2") (pintype "passive"))
      (node (ref "D6") (pin "2") (pinfunction "K_2") (pintype "passive"))
      (node (ref "D7") (pin "2") (pinfunction "K_2") (pintype "passive"))
      (node (ref "D8") (pin "2") (pinfunction "K_2") (pintype "passive"))
      (node (ref "D9") (pin "2") (pinfunction "K_2") (pintype "passive"))
      (node (ref "J1") (pin "4") (pinfunction "4_4") (pintype "passive"))
      (node (ref "U1") (pin "23") (pinfunction "VSS_1_23") (pintype "passive"))
      (node (ref "U1") (pin "35") (pinfunction "VSS_2_35") (pintype "passive"))
      (node (ref "U1") (pin "44") (pinfunction "BOOT0_44") (pintype "passive"))
      (node (ref "U1") (pin "47") (pinfunction "VSS_3_47") (pintype "passive"))
      (node (ref "U1") (pin "5") (pinfunction "OSC_IN_5") (pintype "passive"))
      (node (ref "U1") (pin "6") (pinfunction "OSC_OUT_6") (pintype "passive"))
      (node (ref "U1") (pin "8") (pinfunction "VSSA_8") (pintype "passive"))
      (node (ref "U2") (pin "3") (pinfunction "GND_3") (pintype "passive"))
      (node (ref "U3") (pin "2") (pinfunction "gnd_2") (pintype "passive"))
      (node (ref "U4") (pin "13") (pinfunction "~{OE}_13") (pintype "input"))
      (node (ref "U4") (pin "8") (pinfunction "GND_8") (pintype "power_in"))
      (node (ref "U5") (pin "13") (pinfunction "~{OE}_13") (pintype "input"))
      (node (ref "U5") (pin "8") (pinfunction "GND_8") (pintype "power_in"))
      (node (ref "U6") (pin "13") (pinfunction "~{OE}_13") (pintype "input"))
      (node (ref "U6") (pin "8") (pinfunction "GND_8") (pintype "power_in"))
      (node (ref "U7") (pin "13") (pinfunction "~{OE}_13") (pintype "input"))
      (node (ref "U7") (pin "8") (pinfunction "GND_8") (pintype "power_in"))
      (node (ref "USB1") (pin "GND") (pinfunction "GND_GND") (pintype "passive"))
    )
    (net (code "49") (name "Net-(D1-A)") (class "Default")
      (node (ref "D1") (pin "1") (pinfunction "A_1") (pintype "passive"))
      (node (ref "R6") (pin "1") (pinfunction "1_1") (pintype "passive"))
    )
    (net (code "50") (name "Net-(D2-A)") (class "Default")
      (node (ref "D2") (pin "1") (pinfunction "A_1") (pintype "passive"))
      (node (ref "R7") (pin "1") (pinfunction "1_1") (pintype "passive"))
    )
    (net (code "51") (name "Net-(D3-A)") (class "Default")
      (node (ref "D3") (pin "1") (pinfunction "A_1") (pintype "passive"))
      (node (ref "R8") (pin "1") (pinfunction "1_1") (pintype "passive"))
    )
    (net (code "52") (name "Net-(D4-A)") (class "Default")
      (node (ref "D4") (pin "1") (pinfunction "A_1") (pintype "passive"))
      (node (ref "R9") (pin "1") (pinfunction "1_1") (pintype "passive"))
    )
    (net (code "53") (name "Net-(D5-A)") (class "Default")
      (node (ref "D5") (pin "1") (pinfunction "A_1") (pintype "passive"))
      (node (ref "R10") (pin "1") (pinfunction "1_1") (pintype "passive"))
    )
    (net (code "54") (name "Net-(D6-A)") (class "Default")
      (node (ref "D6") (pin "1") (pinfunction "A_1") (pintype "passive"))
      (node (ref "R11") (pin "1") (pinfunction "1_1") (pintype "passive"))
    )
    (net (code "55") (name "Net-(D7-A)") (class "Default")
      (node (ref "D7") (pin "1") (pinfunction "A_1") (pintype "passive"))
      (node (ref "R12") (pin "1") (pinfunction "1_1") (pintype "passive"))
    )
    (net (code "56") (name "Net-(D8-A)") (class "Default")
      (node (ref "D8") (pin "1") (pinfunction "A_1") (pintype "passive"))
      (node (ref "R13") (pin "1") (pinfunction "1_1") (pintype "passive"))
    )
    (net (code "57") (name "Net-(D9-A)") (class "Default")
      (node (ref "D9") (pin "1") (pinfunction "A_1") (pintype "passive"))
      (node (ref "R14") (pin "1") (pinfunction "1_1") (pintype "passive"))
    )
    (net (code "58") (name "Net-(D10-A)") (class "Default")
      (node (ref "D10") (pin "1") (pinfunction "A_1") (pintype "passive"))
      (node (ref "R15") (pin "1") (pinfunction "1_1") (pintype "passive"))
    )
    (net (code "59") (name "Net-(D11-A)") (class "Default")
      (node (ref "D11") (pin "1") (pinfunction "A_1") (pintype "passive"))
      (node (ref "R16") (pin "1") (pinfunction "1_1") (pintype "passive"))
    )
    (net (code "60") (name "Net-(D12-A)") (class "Default")
      (node (ref "D12") (pin "1") (pinfunction "A_1") (pintype "passive"))
      (node (ref "R17") (pin "1") (pinfunction "1_1") (pintype "passive"))
    )
    (net (code "61") (name "Net-(D13-A)") (class "Default")
      (node (ref "D13") (pin "1") (pinfunction "A_1") (pintype "passive"))
      (node (ref "R18") (pin "1") (pinfunction "1_1") (pintype "passive"))
    )
    (net (code "62") (name "Net-(D14-A)") (class "Default")
      (node (ref "D14") (pin "1") (pinfunction "A_1") (pintype "passive"))
      (node (ref "R19") (pin "1") (pinfunction "1_1") (pintype "passive"))
    )
    (net (code "63") (name "Net-(D15-A)") (class "Default")
      (node (ref "D15") (pin "1") (pinfunction "A_1") (pintype "passive"))
      (node (ref "R20") (pin "1") (pinfunction "1_1") (pintype "passive"))
    )
    (net (code "64") (name "Net-(D16-A)") (class "Default")
      (node (ref "D16") (pin "1") (pinfunction "A_1") (pintype "passive"))
      (node (ref "R21") (pin "1") (pinfunction "1_1") (pintype "passive"))
    )
    (net (code "65") (name "Net-(D17-A)") (class "Default")
      (node (ref "D17") (pin "1") (pinfunction "A_1") (pintype "passive"))
      (node (ref "R22") (pin "1") (pinfunction "1_1") (pintype "passive"))
    )
    (net (code "66") (name "Net-(D18-A)") (class "Default")
      (node (ref "D18") (pin "1") (pinfunction "A_1") (pintype "passive"))
      (node (ref "R23") (pin "1") (pinfunction "1_1") (pintype "passive"))
    )
    (net (code "67") (name "Net-(D19-A)") (class "Default")
      (node (ref "D19") (pin "1") (pinfunction "A_1") (pintype "passive"))
      (node (ref "R24") (pin "1") (pinfunction "1_1") (pintype "passive"))
    )
    (net (code "68") (name "Net-(D20-A)") (class "Default")
      (node (ref "D20") (pin "1") (pinfunction "A_1") (pintype "passive"))
      (node (ref "R25") (pin "1") (pinfunction "1_1") (pintype "passive"))
    )
    (net (code "69") (name "Net-(D21-A)") (class "Default")
      (node (ref "D21") (pin "1") (pinfunction "A_1") (pintype "passive"))
      (node (ref "R26") (pin "1") (pinfunction "1_1") (pintype "passive"))
    )
    (net (code "70") (name "Net-(D22-A)") (class "Default")
      (node (ref "D22") (pin "1") (pinfunction "A_1") (pintype "passive"))
      (node (ref "R27") (pin "1") (pinfunction "1_1") (pintype "passive"))
    )
    (net (code "71") (name "Net-(D23-A)") (class "Default")
      (node (ref "D23") (pin "1") (pinfunction "A_1") (pintype "passive"))
      (node (ref "R28") (pin "1") (pinfunction "1_1") (pintype "passive"))
    )
    (net (code "72") (name "Net-(D24-A)") (class "Default")
      (node (ref "D24") (pin "1") (pinfunction "A_1") (pintype "passive"))
      (node (ref "R29") (pin "1") (pinfunction "1_1") (pintype "passive"))
    )
    (net (code "73") (name "Net-(D25-A)") (class "Default")
      (node (ref "D25") (pin "1") (pinfunction "A_1") (pintype "passive"))
      (node (ref "R30") (pin "1") (pinfunction "1_1") (pintype "passive"))
    )
    (net (code "74") (name "Net-(D26-A)") (class "Default")
      (node (ref "D26") (pin "1") (pinfunction "A_1") (pintype "passive"))
      (node (ref "R31") (pin "1") (pinfunction "1_1") (pintype "passive"))
    )
    (net (code "75") (name "Net-(D27-A)") (class "Default")
      (node (ref "D27") (pin "1") (pinfunction "A_1") (pintype "passive"))
      (node (ref "R32") (pin "1") (pinfunction "1_1") (pintype "passive"))
    )
    (net (code "76") (name "Net-(D28-A)") (class "Default")
      (node (ref "D28") (pin "1") (pinfunction "A_1") (pintype "passive"))
      (node (ref "R33") (pin "1") (pinfunction "1_1") (pintype "passive"))
    )
    (net (code "77") (name "Net-(D29-A)") (class "Default")
      (node (ref "D29") (pin "1") (pinfunction "A_1") (pintype "passive"))
      (node (ref "R34") (pin "1") (pinfunction "1_1") (pintype "passive"))
    )
    (net (code "78") (name "Net-(D30-A)") (class "Default")
      (node (ref "D30") (pin "1") (pinfunction "A_1") (pintype "passive"))
      (node (ref "R35") (pin "1") (pinfunction "1_1") (pintype "passive"))
    )
    (net (code "79") (name "Net-(D31-A)") (class "Default")
      (node (ref "D31") (pin "1") (pinfunction "A_1") (pintype "passive"))
      (node (ref "R39") (pin "1") (pinfunction "1_1") (pintype "passive"))
    )
    (net (code "80") (name "Net-(D32-A)") (class "Default")
      (node (ref "D32") (pin "1") (pinfunction "A_1") (pintype "passive"))
      (node (ref "R40") (pin "1") (pinfunction "1_1") (pintype "passive"))
    )
    (net (code "81") (name "Net-(U2-V3)") (class "Default")
      (node (ref "C2") (pin "2") (pinfunction "2_2") (pintype "passive"))
      (node (ref "U2") (pin "10") (pinfunction "V3_10") (pintype "passive"))
    )
    (net (code "82") (name "Net-(U4-SDO)") (class "Default")
      (node (ref "U4") (pin "9") (pinfunction "SDO_9") (pintype "output"))
      (node (ref "U5") (pin "14") (pinfunction "SDI_14") (pintype "input"))
    )
    (net (code "83") (name "Net-(U5-SDO)") (class "Default")
      (node (ref "U5") (pin "9") (pinfunction "SDO_9") (pintype "output"))
      (node (ref "U6") (pin "14") (pinfunction "SDI_14") (pintype "input"))
    )
    (net (code "84") (name "Net-(U6-SDO)") (class "Default")
      (node (ref "U6") (pin "9") (pinfunction "SDO_9") (pintype "output"))
      (node (ref "U7") (pin "14") (pinfunction "SDI_14") (pintype "input"))
    )
    (net (code "85") (name "VBUS") (class "Default")
      (node (ref "C11") (pin "2") (pinfunction "2_2") (pintype "passive"))
      (node (ref "C3") (pin "2") (pinfunction "2_2") (pintype "passive"))
      (node (ref "C8") (pin "2") (pinfunction "2_2") (pintype "passive"))
      (node (ref "R36") (pin "2") (pinfunction "2_2") (pintype "passive"))
      (node (ref "R37") (pin "2") (pinfunction "2_2") (pintype "passive"))
      (node (ref "R38") (pin "2") (pinfunction "2_2") (pintype "passive"))
      (node (ref "U2") (pin "7") (pinfunction "VCC_7") (pintype "passive"))
      (node (ref "U3") (pin "1") (pinfunction "5v_1") (pintype "passive"))
      (node (ref "U3") (pin "3") (pinfunction "en_3") (pintype "passive"))
      (node (ref "U4") (pin "10") (pinfunction "~{SCLR}_10") (pintype "input"))
      (node (ref "U4") (pin "16") (pinfunction "VDD_16") (pintype "power_in"))
      (node (ref "U5") (pin "10") (pinfunction "~{SCLR}_10") (pintype "input"))
      (node (ref "U5") (pin "16") (pinfunction "VDD_16") (pintype "power_in"))
      (node (ref "U6") (pin "10") (pinfunction "~{SCLR}_10") (pintype "input"))
      (node (ref "U6") (pin "16") (pinfunction "VDD_16") (pintype "power_in"))
      (node (ref "U7") (pin "10") (pinfunction "~{SCLR}_10") (pintype "input"))
      (node (ref "U7") (pin "16") (pinfunction "VDD_16") (pintype "power_in"))
      (node (ref "USB1") (pin "VBUS") (pinfunction "VBUS_VBUS") (pintype "passive"))
    )
    (net (code "86") (name "VCC3") (class "Default")
      (node (ref "C4") (pin "2") (pinfunction "2_2") (pintype "passive"))
      (node (ref "C5") (pin "2") (pinfunction "2_2") (pintype "passive"))
      (node (ref "C6") (pin "2") (pinfunction "2_2") (pintype "passive"))
      (node (ref "C7") (pin "2") (pinfunction "2_2") (pintype "passive"))
      (node (ref "C9") (pin "2") (pinfunction "2_2") (pintype "passive"))
      (node (ref "J1") (pin "1") (pinfunction "1_1") (pintype "passive"))
      (node (ref "R1") (pin "1") (pinfunction "1_1") (pintype "passive"))
      (node (ref "R2") (pin "1") (pinfunction "1_1") (pintype "passive"))
      (node (ref "R3") (pin "1") (pinfunction "1_1") (pintype "passive"))
      (node (ref "R4") (pin "1") (pinfunction "1_1") (pintype "passive"))
      (node (ref "R5") (pin "1") (pinfunction "1_1") (pintype "passive"))
      (node (ref "U1") (pin "1") (pinfunction "VBAT_1") (pintype "passive"))
      (node (ref "U1") (pin "24") (pinfunction "VDD_1_24") (pintype "passive"))
      (node (ref "U1") (pin "36") (pinfunction "VDD_2_36") (pintype "passive"))
      (node (ref "U1") (pin "48") (pinfunction "VDD_3_48") (pintype "passive"))
      (node (ref "U1") (pin "9") (pinfunction "VDDA_9") (pintype "passive"))
      (node (ref "U3") (pin "5") (pinfunction "3v3_5") (pintype "passive"))
    )
    (net (code "87") (name "unconnected-(U1-PA0{slash}WKUP{slash}ADC123_IN0{slash}T2C1ETR{slash}T5C1{slash}T8ETR-Pad10)") (class "Default")
      (node (ref "U1") (pin "10") (pinfunction "PA0/WKUP/ADC123_IN0/T2C1ETR/T5C1/T8ETR_10") (pintype "passive"))
    )
    (net (code "88") (name "unconnected-(U1-PA1{slash}ADC123_IN1{slash}T5C2{slash}T2C2-Pad11)") (class "Default")
      (node (ref "U1") (pin "11") (pinfunction "PA1/ADC123_IN1/T5C2/T2C2_11") (pintype "passive"))
    )
    (net (code "89") (name "unconnected-(U1-PA2{slash}ADC123_IN2{slash}USART2_Tx{slash}T5C3{slash}T2C3-Pad12)") (class "Default")
      (node (ref "U1") (pin "12") (pinfunction "PA2/ADC123_IN2/USART2_Tx/T5C3/T2C3_12") (pintype "passive"))
    )
    (net (code "90") (name "unconnected-(U1-PA4{slash}ADC123_IN4{slash}DAC_OUT1{slash}SPI1_NSS-Pad14)") (class "Default")
      (node (ref "U1") (pin "14") (pinfunction "PA4/ADC123_IN4/DAC_OUT1/SPI1_NSS_14") (pintype "passive"))
    )
    (net (code "91") (name "unconnected-(U1-PA5{slash}ADC123_IN5{slash}DAC_OUT2{slash}SPI1_SCK-Pad15)") (class "Default")
      (node (ref "U1") (pin "15") (pinfunction "PA5/ADC123_IN5/DAC_OUT2/SPI1_SCK_15") (pintype "passive"))
    )
    (net (code "92") (name "unconnected-(U1-PA8{slash}T1C1{slash}MCO-Pad29)") (class "Default")
      (node (ref "U1") (pin "29") (pinfunction "PA8/T1C1/MCO_29") (pintype "passive"))
    )
    (net (code "93") (name "unconnected-(U1-PA11{slash}CAN_Rx{slash}T1C4{slash}USBDM-Pad32)") (class "Default")
      (node (ref "U1") (pin "32") (pinfunction "PA11/CAN_Rx/T1C4/USBDM_32") (pintype "passive"))
    )
    (net (code "94") (name "unconnected-(U1-PA12{slash}CAN_Tx{slash}T1ETR{slash}USBDP-Pad33)") (class "Default")
      (node (ref "U1") (pin "33") (pinfunction "PA12/CAN_Tx/T1ETR/USBDP_33") (pintype "passive"))
    )
    (net (code "95") (name "unconnected-(U1-PA15{slash}JTDI{slash}I2S3_WS{slash}JTDI{slash}T2C1ETR{slash}SPI3_NSS-Pad38)") (class "Default")
      (node (ref "U1") (pin "38") (pinfunction "PA15/JTDI/I2S3_WS/JTDI/T2C1ETR/SPI3_NSS_38") (pintype "passive"))
    )
    (net (code "96") (name "unconnected-(U1-PB2{slash}BOOT1-Pad20)") (class "Default")
      (node (ref "U1") (pin "20") (pinfunction "PB2/BOOT1_20") (pintype "passive"))
    )
    (net (code "97") (name "unconnected-(U1-PB3{slash}JTDO{slash}SPI3_SCK{slash}I2S3_CK{slash}T2C2{slash}SPI1_SCK-Pad39)") (class "Default")
      (node (ref "U1") (pin "39") (pinfunction "PB3/JTDO/SPI3_SCK/I2S3_CK/T2C2/SPI1_SCK_39") (pintype "passive"))
    )
    (net (code "98") (name "unconnected-(U1-PB4{slash}NJTRST{slash}SPI3_MISO{slash}T3C1{slash}SPI1_MISO-Pad40)") (class "Default")
      (node (ref "U1") (pin "40") (pinfunction "PB4/NJTRST/SPI3_MISO/T3C1/SPI1_MISO_40") (pintype "passive"))
    )
    (net (code "99") (name "unconnected-(U1-PB8{slash}SDIO_D4{slash}I2C1_SCL{slash}T4C3(7){slash}CAN_Rx-Pad45)") (class "Default")
      (node (ref "U1") (pin "45") (pinfunction "PB8/SDIO_D4/I2C1_SCL/T4C3(7)/CAN_Rx_45") (pintype "passive"))
    )
    (net (code "100") (name "unconnected-(U1-PB9{slash}SDIO_D5{slash}I2C1_SDA{slash}T4C4{slash}CAN_Tx-Pad46)") (class "Default")
      (node (ref "U1") (pin "46") (pinfunction "PB9/SDIO_D5/I2C1_SDA/T4C4/CAN_Tx_46") (pintype "passive"))
    )
    (net (code "101") (name "unconnected-(U1-PB10{slash}USART3_Tx{slash}I2C2_SCL{slash}T2C3-Pad21)") (class "Default")
      (node (ref "U1") (pin "21") (pinfunction "PB10/USART3_Tx/I2C2_SCL/T2C3_21") (pintype "passive"))
    )
    (net (code "102") (name "unconnected-(U1-PB11{slash}USART3_Rx{slash}I2C2_SDA{slash}T2C4-Pad22)") (class "Default")
      (node (ref "U1") (pin "22") (pinfunction "PB11/USART3_Rx/I2C2_SDA/T2C4_22") (pintype "passive"))
    )
    (net (code "103") (name "unconnected-(U1-PB12{slash}I2S2_WS{slash}T1BKIN{slash}SPI2_NSS{slash}I2C2_SMBA-Pad25)") (class "Default")
      (node (ref "U1") (pin "25") (pinfunction "PB12/I2S2_WS/T1BKIN/SPI2_NSS/I2C2_SMBA_25") (pintype "passive"))
    )
    (net (code "104") (name "unconnected-(U1-PB13{slash}I2S2_CK{slash}T1CH1N{slash}SPI2_SCK-Pad26)") (class "Default")
      (node (ref "U1") (pin "26") (pinfunction "PB13/I2S2_CK/T1CH1N/SPI2_SCK_26") (pintype "passive"))
    )
    (net (code "105") (name "unconnected-(U1-PB14{slash}T1CH2N{slash}SPI2_MISO-Pad27)") (class "Default")
      (node (ref "U1") (pin "27") (pinfunction "PB14/T1CH2N/SPI2_MISO_27") (pintype "passive"))
    )
    (net (code "106") (name "unconnected-(U1-PB15{slash}I2S2_SD{slash}T1CH3N{slash}SPI2_MOSI-Pad28)") (class "Default")
      (node (ref "U1") (pin "28") (pinfunction "PB15/I2S2_SD/T1CH3N/SPI2_MOSI_28") (pintype "passive"))
    )
    (net (code "107") (name "unconnected-(U1-PC13-TAMPER-RTC-Pad2)") (class "Default")
      (node (ref "U1") (pin "2") (pinfunction "PC13-TAMPER-RTC_2") (pintype "passive"))
    )
    (net (code "108") (name "unconnected-(U1-PC14-OSC32_IN-Pad3)") (class "Default")
      (node (ref "U1") (pin "3") (pinfunction "PC14-OSC32_IN_3") (pintype "passive"))
    )
    (net (code "109") (name "unconnected-(U1-PC15-OSC32_OUT-Pad4)") (class "Default")
      (node (ref "U1") (pin "4") (pinfunction "PC15-OSC32_OUT_4") (pintype "passive"))
    )
    (net (code "110") (name "unconnected-(U2-CTS-Pad5)") (class "Default")
      (node (ref "U2") (pin "5") (pinfunction "CTS_5") (pintype "passive"))
    )
    (net (code "111") (name "unconnected-(U2-RTS-Pad4)") (class "Default")
      (node (ref "U2") (pin "4") (pinfunction "RTS_4") (pintype "passive"))
    )
    (net (code "112") (name "unconnected-(U2-TNOW-Pad6)") (class "Default")
      (node (ref "U2") (pin "6") (pinfunction "TNOW_6") (pintype "passive"))
    )
    (net (code "113") (name "unconnected-(U3-nc-Pad4)") (class "Default")
      (node (ref "U3") (pin "4") (pinfunction "nc_4") (pintype "passive"))
    )
    (net (code "114") (name "unconnected-(U7-SDO-Pad9)") (class "Default")
      (node (ref "U7") (pin "9") (pinfunction "SDO_9") (pintype "output"))
    )
    (net (code "115") (name "unconnected-(USB1-CC2-PadCC1)") (class "Default")
      (node (ref "USB1") (pin "CC1") (pinfunction "CC2_CC1") (pintype "passive"))
    )
    (net (code "116") (name "unconnected-(USB1-PadCC1)") (class "Default")
      (node (ref "USB1") (pin "CC1") (pinfunction "CC1_CC1") (pintype "passive"))
    )
    (net (code "117") (name "unconnected-(USB1-PadSBU1)") (class "Default")
      (node (ref "USB1") (pin "SBU1") (pinfunction "SBU1_SBU1") (pintype "passive"))
    )
    (net (code "118") (name "unconnected-(USB1-PadSBU2)") (class "Default")
      (node (ref "USB1") (pin "SBU2") (pinfunction "SBU2_SBU2") (pintype "passive"))
    )
  )
)
